# PWR.net
KiCad netlist of a schematic drawn in Altium Designer
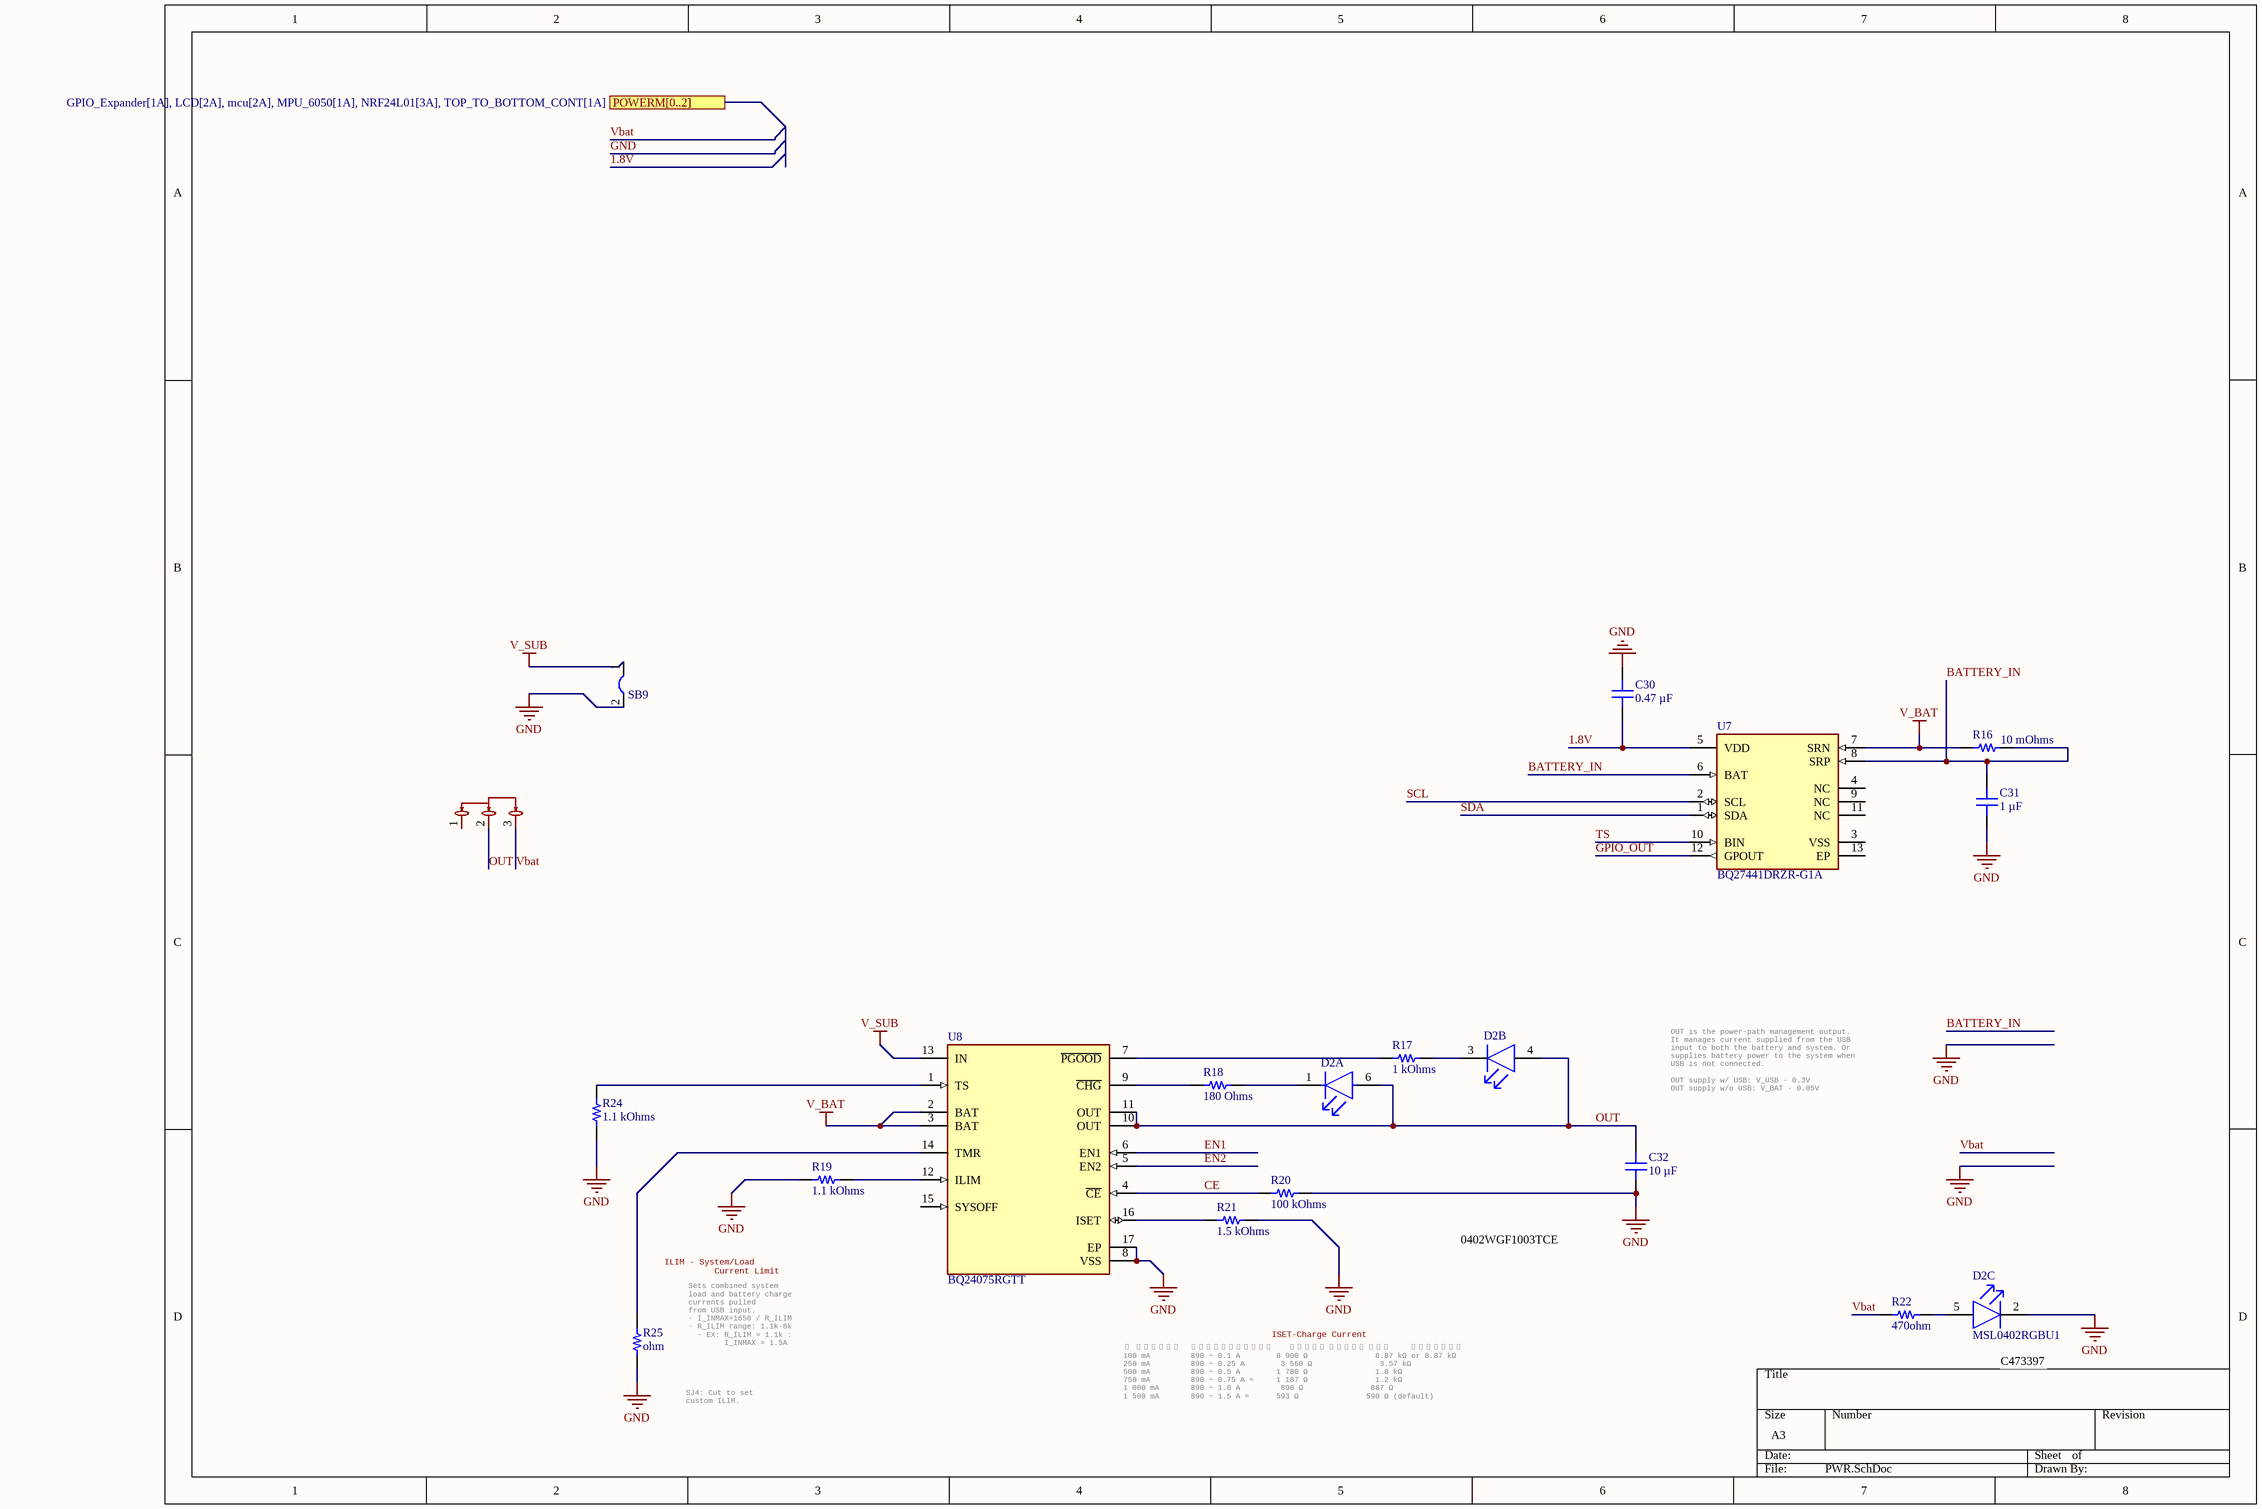
[diagram p0: PWR.SchDoc]

(export (version "E")
  (design (tool "Eeschema 10.0.6"))
  (components
    (comp (ref "C30")
      (value "~")
      (footprint "CAP 0402_1005")
      (description "CAP CER 0.47UF 35V X5R 0402")
      (fields
        (field (name "CAPACITANCE") "0.47 µF")
        (field (name "MFR.PART #") "GRM155R61A474KE15D")
        (field (name "JLCPCB PART #") "C77003")
      )
      (libsource (lib "Celestial Altium Library - altium_library") (part "Capacitor"))
    )
    (comp (ref "C31")
      (value "~")
      (footprint "MURATA GRM155 0402_1005")
      (description "CAP CER 1UF 10V X7S 0402")
      (fields
        (field (name "CAPACITANCE") "1 µF")
        (field (name "MFR.PART #") "GRM155R60J105KE19D")
        (field (name "JLCPCB PART #") "C15684")
      )
      (libsource (lib "Celestial Altium Library - altium_library") (part "Capacitor"))
    )
    (comp (ref "C32")
      (value "10 µF")
      (footprint "CAP 0402_1005")
      (description "CAP CER 10UF 10V X5R 0402")
      (fields (field (name "MFR.PART #") "CL05A106MQ5NUNC") (field (name "JLCPCB PART #") "C15525"))
      (libsource (lib "Celestial Altium Library - altium_library") (part "Capacitor"))
    )
    (comp (ref "D2")
      (value "MSL0402RGBU1")
      (footprint "FP-MSL0402-MFG")
      (description "LED RGB DIFFUSED 1816 SMD")
      (fields (field (name "JLCPCB PART #") "C2898980") (field (name "MANUFACTURER") "ROHM Semicon"))
      (libsource (lib "Altium Content Vault") (part "4114c7771f6fc78b8afd566e2a29b32"))
    )
    (comp (ref "R16")
      (value "10 mOhms")
      (footprint "RES 0402_1005")
      (description "RES 0.01 OHM 5% 1/5W 0402")
      (fields (field (name "MFR.PART #") "PE0402FRF070R01L") (field (name "JLCPCB PART #") "C2089431"))
      (libsource (lib "Celestial Altium Library - altium_library") (part "Resistor"))
    )
    (comp (ref "R17")
      (value "1 kOhms")
      (footprint "RES 0402_1005")
      (description "RES 1 KOHMS 0.1% 1/16W 0402")
      (fields (field (name "MFR.PART #") "0402WGF1001TCE") (field (name "JLCPCB PART #") "C11702"))
      (libsource (lib "Celestial Altium Library - altium_library") (part "Resistor"))
    )
    (comp (ref "R18")
      (value "180 Ohms")
      (footprint "YAGEO RES 0402_1005")
      (description "RES SMD 180 OHM 0.1% 1/16W 0402")
      (fields (field (name "MFR.PART #") "C38941") (field (name "JLCPCB PART #") "0402WGF1800TCE"))
      (libsource (lib "Celestial Altium Library - altium_library") (part "Resistor"))
    )
    (comp (ref "R19")
      (value "1.1 kOhms")
      (footprint "YAGEO RES 0402_1005")
      (description "RES 1.1K OHM 1% 1/16W 0402")
      (fields (field (name "MFR.PART #") "0402WGF1101TCE") (field (name "JLCPCB PART #") "C25860"))
      (libsource (lib "Celestial Altium Library - altium_library") (part "Resistor"))
    )
    (comp (ref "R20")
      (value "100 kOhms")
      (footprint "RES 0402_1005")
      (description "RES 100K OHM 0.1% 1/10W 0402")
      (fields (field (name "MFR.PART #") "0402WGF1003TCE") (field (name "JLCPCB PART #") "0402"))
      (libsource (lib "Celestial Altium Library - altium_library") (part "Resistor"))
    )
    (comp (ref "R21")
      (value "1.5 kOhms")
      (footprint "RES 0402_1005")
      (description "RES SMD 1.5K OHM 0.5% 1/16W 0402")
      (fields (field (name "MFR.PART #") "CRCW04021K50FKED") (field (name "JLCPCB PART #") "C71622"))
      (libsource (lib "Celestial Altium Library - altium_library") (part "Resistor"))
    )
    (comp (ref "R22")
      (value "470ohm")
      (footprint "RES 0402_1005")
      (description "RES SMD 1.5K OHM 0.5% 1/16W 0402")
      (fields (field (name "MFR.PART #") "0402WGF1501TCE") (field (name "JLCPCB PART #") "C25867"))
      (libsource (lib "Celestial Altium Library - altium_library") (part "Resistor"))
    )
    (comp (ref "R24")
      (value "1.1 kOhms")
      (footprint "YAGEO RES 0402_1005")
      (description "RES 1.1K OHM 1% 1/16W 0402")
      (fields (field (name "MFR.PART #") "0402WGF1101TCE") (field (name "JLCPCB PART #") "C25860"))
      (libsource (lib "Celestial Altium Library - altium_library") (part "Resistor"))
    )
    (comp (ref "R25")
      (value "ohm")
      (footprint "YAGEO RES 0402_1005")
      (description "RES 1.1K OHM 1% 1/16W 0402")
      (fields (field (name "MFR.PART #") "0402WGF0000TCE") (field (name "JLCPCB PART #") "C17168"))
      (libsource (lib "Celestial Altium Library - altium_library") (part "Resistor"))
    )
    (comp (ref "SB9")
      (value "Jumper")
      (footprint "Jumper")
      (libsource (lib "Integrated_Library2") (part "Jumper"))
    )
    (comp (ref "SW2")
      (value "MST-12D18G4 SPDT Slide Switch")
      (footprint "SW-SMD_MST-12D18G4-SPDT-SLIDE-SWITCH")
      (fields (field (name "MFR.PART #") "C49023767") (field (name "MANUFACTURER") "SHOU HAN"))
      (libsource (lib "altium-import") (part "root_0_MST-12D18G4 SPDT Slide Switch_"))
    )
    (comp (ref "U7")
      (value "BQ27441DRZR-G1A")
      (footprint "FP-DRZ0012A-MFG")
      (description "IC BATT FUEL GAUGE LI-ION 12SON")
      (fields (field (name "JLCPCB PART #") "C473397") (field (name "MANUFACTURER") "Texas Instruments"))
      (libsource (lib "Altium Content Vault") (part "0f562f18464a1f07b55dcd927f1fdf2"))
    )
    (comp (ref "U8")
      (value "BQ24075RGTT")
      (footprint "FP-RGT0016C-IPC_C")
      (description "IC LI-ION CHARGE/PWR MGMT 16-QFN")
      (fields (field (name "JLCPCB PART #") "C2865459") (field (name "MANUFACTURER") "Texas Instruments"))
      (libsource (lib "Altium Content Vault") (part "55f6c111728d334b4104933744ca2f6"))
    )
  )
  (nets
    (net (code "4") (name "/1.8V") (class "Default")
      (node (ref "C30") (pin "2") (pinfunction "2_2") (pintype "passive"))
      (node (ref "U7") (pin "5") (pinfunction "VDD_5") (pintype "power_in"))
    )
    (net (code "5") (name "/BATTERY_IN") (class "Default")
      (node (ref "C31") (pin "2") (pinfunction "2_2") (pintype "passive"))
      (node (ref "R16") (pin "2") (pinfunction "2_2") (pintype "passive"))
      (node (ref "U7") (pin "6") (pinfunction "BAT_6") (pintype "input"))
      (node (ref "U7") (pin "8") (pinfunction "SRP_8") (pintype "input"))
    )
    (net (code "6") (name "/CE") (class "Default")
      (node (ref "R20") (pin "2") (pinfunction "2_2") (pintype "passive"))
      (node (ref "U8") (pin "4") (pinfunction "~{CE}_4") (pintype "input"))
    )
    (net (code "7") (name "/EN1") (class "Default")
      (node (ref "U8") (pin "6") (pinfunction "EN1_6") (pintype "input"))
    )
    (net (code "8") (name "/EN2") (class "Default")
      (node (ref "U8") (pin "5") (pinfunction "EN2_5") (pintype "input"))
    )
    (net (code "9") (name "/GPIO_OUT") (class "Default")
      (node (ref "U7") (pin "12") (pinfunction "GPOUT_12") (pintype "output"))
    )
    (net (code "10") (name "/OUT") (class "Default")
      (node (ref "C32") (pin "2") (pinfunction "2_2") (pintype "passive"))
      (node (ref "D2") (pin "4") (pinfunction "RED_A_4") (pintype "passive"))
      (node (ref "D2") (pin "6") (pinfunction "BLUE_A_6") (pintype "passive"))
      (node (ref "SW2") (pin "2") (pinfunction "2_2") (pintype "passive"))
      (node (ref "U8") (pin "10") (pinfunction "OUT_10") (pintype "power_in"))
      (node (ref "U8") (pin "11") (pinfunction "OUT_11") (pintype "power_in"))
    )
    (net (code "12") (name "/SCL") (class "Default")
      (node (ref "U7") (pin "2") (pinfunction "SCL_2") (pintype "bidirectional"))
    )
    (net (code "13") (name "/SDA") (class "Default")
      (node (ref "U7") (pin "1") (pinfunction "SDA_1") (pintype "bidirectional"))
    )
    (net (code "14") (name "/TS") (class "Default")
      (node (ref "U7") (pin "10") (pinfunction "BIN_10") (pintype "input"))
    )
    (net (code "15") (name "/Vbat") (class "Default")
      (node (ref "R22") (pin "1") (pinfunction "1_1") (pintype "passive"))
      (node (ref "SW2") (pin "3") (pinfunction "3_3") (pintype "passive"))
    )
    (net (code "16") (name "GND") (class "Default")
      (node (ref "C30") (pin "1") (pinfunction "1_1") (pintype "passive"))
      (node (ref "C31") (pin "1") (pinfunction "1_1") (pintype "passive"))
      (node (ref "C32") (pin "1") (pinfunction "1_1") (pintype "passive"))
      (node (ref "D2") (pin "2") (pinfunction "GREEN_C_2") (pintype "passive"))
      (node (ref "R19") (pin "1") (pinfunction "1_1") (pintype "passive"))
      (node (ref "R20") (pin "1") (pinfunction "1_1") (pintype "passive"))
      (node (ref "R21") (pin "2") (pinfunction "2_2") (pintype "passive"))
      (node (ref "R24") (pin "1") (pinfunction "1_1") (pintype "passive"))
      (node (ref "R25") (pin "1") (pinfunction "1_1") (pintype "passive"))
      (node (ref "SB9") (pin "2") (pinfunction "2_2") (pintype "passive"))
      (node (ref "U8") (pin "17") (pinfunction "EP_17") (pintype "power_in"))
      (node (ref "U8") (pin "8") (pinfunction "VSS_8") (pintype "power_in"))
    )
    (net (code "17") (name "Net-(D2A-BLUE_C)") (class "Default")
      (node (ref "D2") (pin "1") (pinfunction "BLUE_C_1") (pintype "passive"))
      (node (ref "R18") (pin "1") (pinfunction "1_1") (pintype "passive"))
    )
    (net (code "18") (name "Net-(D2B-RED_C)") (class "Default")
      (node (ref "D2") (pin "3") (pinfunction "RED_C_3") (pintype "passive"))
      (node (ref "R17") (pin "2") (pinfunction "2_2") (pintype "passive"))
    )
    (net (code "19") (name "Net-(D2C-GREEN_A)") (class "Default")
      (node (ref "D2") (pin "5") (pinfunction "GREEN_A_5") (pintype "passive"))
      (node (ref "R22") (pin "2") (pinfunction "2_2") (pintype "passive"))
    )
    (net (code "20") (name "Net-(U8-ILIM)") (class "Default")
      (node (ref "R19") (pin "2") (pinfunction "2_2") (pintype "passive"))
      (node (ref "U8") (pin "12") (pinfunction "ILIM_12") (pintype "input"))
    )
    (net (code "21") (name "Net-(U8-ISET)") (class "Default")
      (node (ref "R21") (pin "1") (pinfunction "1_1") (pintype "passive"))
      (node (ref "U8") (pin "16") (pinfunction "ISET_16") (pintype "bidirectional"))
    )
    (net (code "22") (name "Net-(U8-TMR)") (class "Default")
      (node (ref "R25") (pin "2") (pinfunction "2_2") (pintype "passive"))
      (node (ref "U8") (pin "14") (pinfunction "TMR_14") (pintype "passive"))
    )
    (net (code "23") (name "Net-(U8-TS)") (class "Default")
      (node (ref "R24") (pin "2") (pinfunction "2_2") (pintype "passive"))
      (node (ref "U8") (pin "1") (pinfunction "TS_1") (pintype "input"))
    )
    (net (code "24") (name "Net-(U8-~{CHG})") (class "Default")
      (node (ref "R18") (pin "2") (pinfunction "2_2") (pintype "passive"))
      (node (ref "U8") (pin "9") (pinfunction "~{CHG}_9") (pintype "tri_state"))
    )
    (net (code "25") (name "Net-(U8-~{PGOOD})") (class "Default")
      (node (ref "R17") (pin "1") (pinfunction "1_1") (pintype "passive"))
      (node (ref "U8") (pin "7") (pinfunction "~{PGOOD}_7") (pintype "tri_state"))
    )
    (net (code "26") (name "V_BAT") (class "Default")
      (node (ref "R16") (pin "1") (pinfunction "1_1") (pintype "passive"))
      (node (ref "U7") (pin "7") (pinfunction "SRN_7") (pintype "input"))
      (node (ref "U8") (pin "2") (pinfunction "BAT_2") (pintype "power_in"))
      (node (ref "U8") (pin "3") (pinfunction "BAT_3") (pintype "power_in"))
    )
    (net (code "27") (name "V_SUB") (class "Default")
      (node (ref "SB9") (pin "1") (pinfunction "1_1") (pintype "passive"))
      (node (ref "U8") (pin "13") (pinfunction "IN_13") (pintype "power_in"))
    )
    (net (code "28") (name "unconnected-(SW2-Pad1)") (class "Default")
      (node (ref "SW2") (pin "1") (pinfunction "1_1") (pintype "passive"))
    )
    (net (code "29") (name "unconnected-(U7-EP-Pad13)") (class "Default")
      (node (ref "U7") (pin "13") (pinfunction "EP_13") (pintype "power_in"))
    )
    (net (code "30") (name "unconnected-(U7-NC-Pad4)") (class "Default")
      (node (ref "U7") (pin "4") (pinfunction "NC_4") (pintype "passive"))
    )
    (net (code "31") (name "unconnected-(U7-NC-Pad9)") (class "Default")
      (node (ref "U7") (pin "9") (pinfunction "NC_9") (pintype "passive"))
    )
    (net (code "32") (name "unconnected-(U7-NC-Pad11)") (class "Default")
      (node (ref "U7") (pin "11") (pinfunction "NC_11") (pintype "passive"))
    )
    (net (code "33") (name "unconnected-(U7-VSS-Pad3)") (class "Default")
      (node (ref "U7") (pin "3") (pinfunction "VSS_3") (pintype "power_in"))
    )
    (net (code "34") (name "unconnected-(U8-SYSOFF-Pad15)") (class "Default")
      (node (ref "U8") (pin "15") (pinfunction "SYSOFF_15") (pintype "input"))
    )
  )
)
